# Loop_Mux_V2.net
KiCad netlist of a schematic drawn in EAGLE
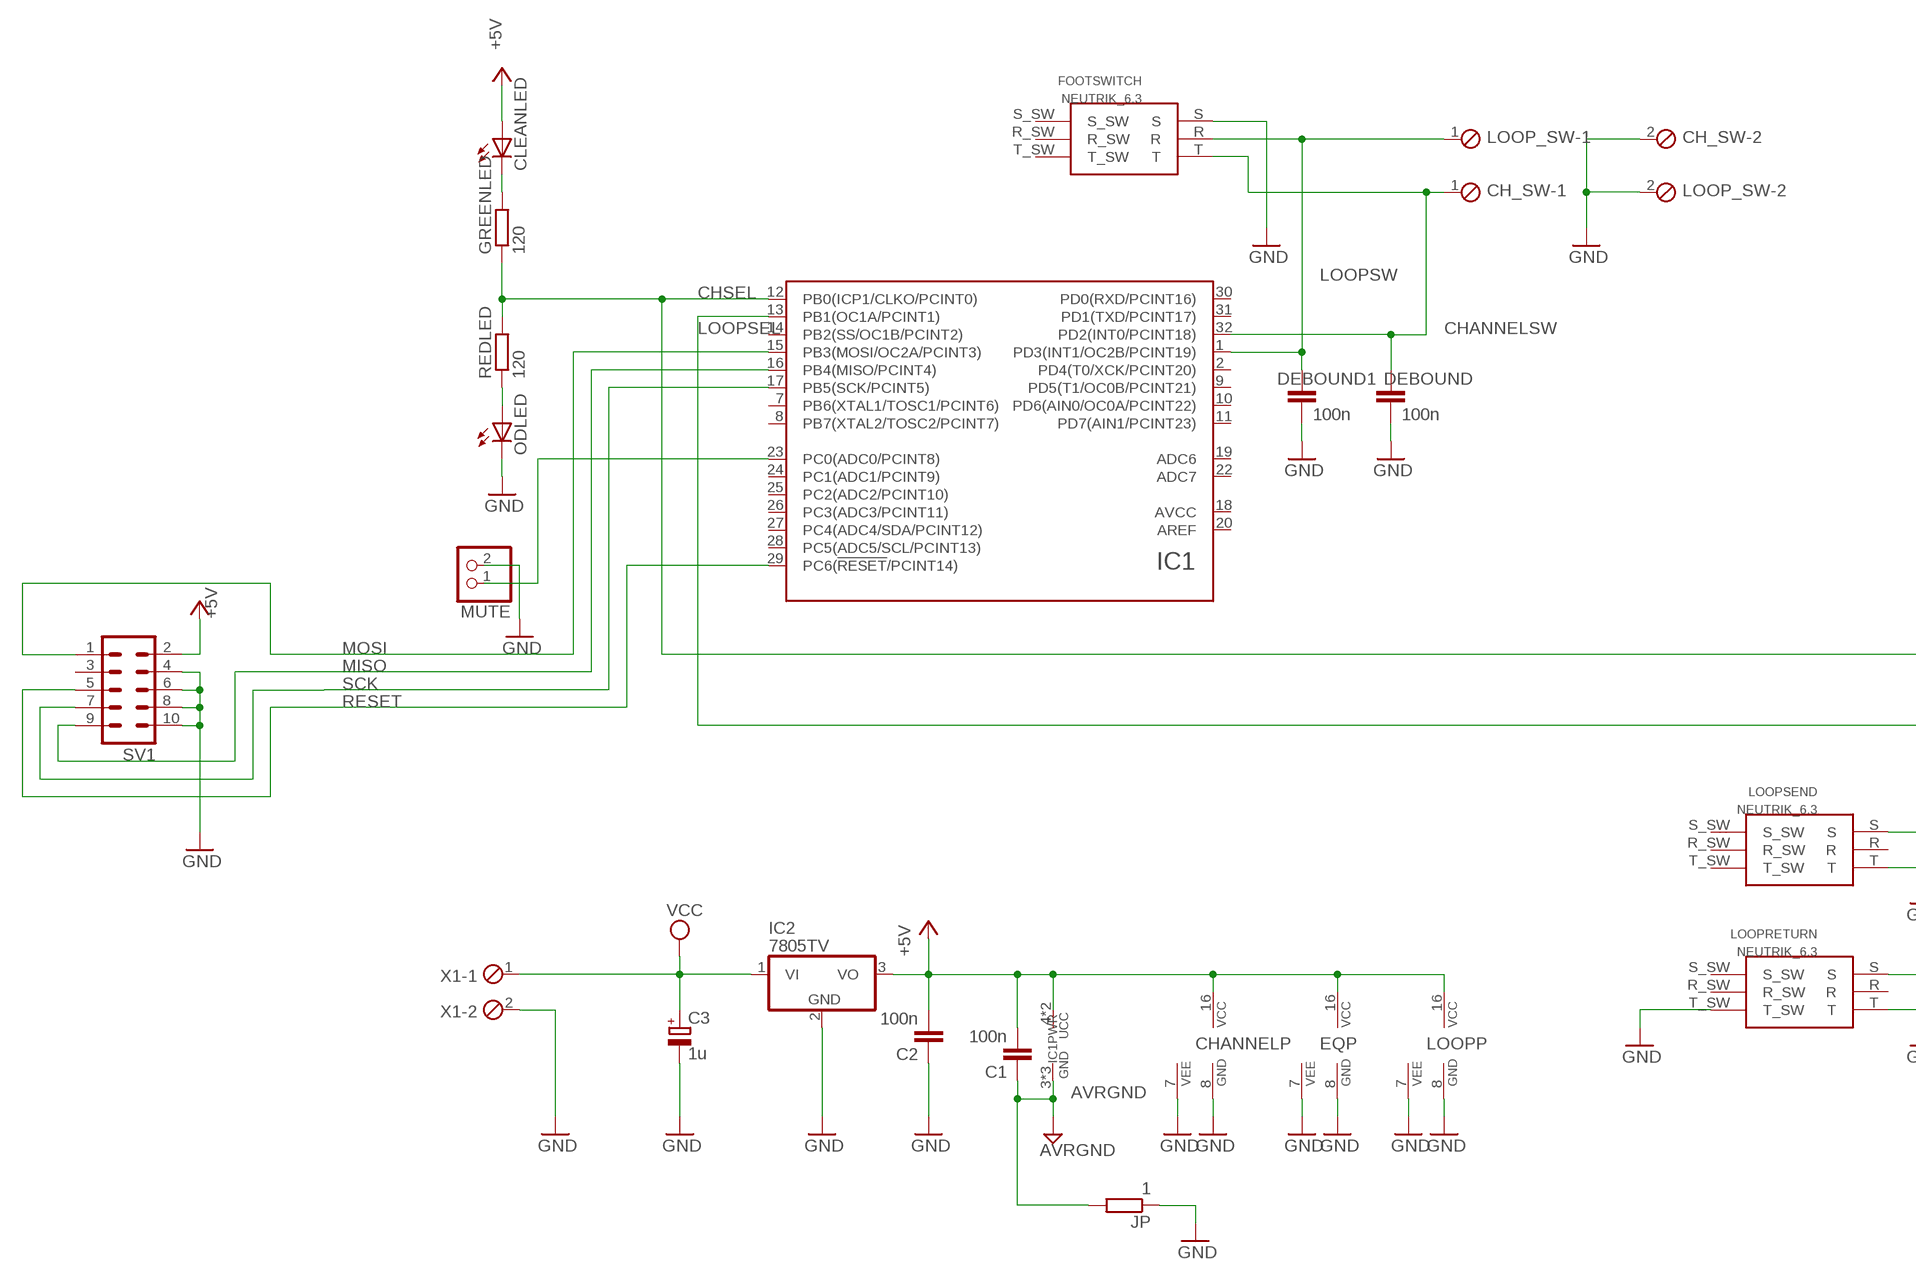
[diagram p0: schematic, sheet 1, part 1 of 2]
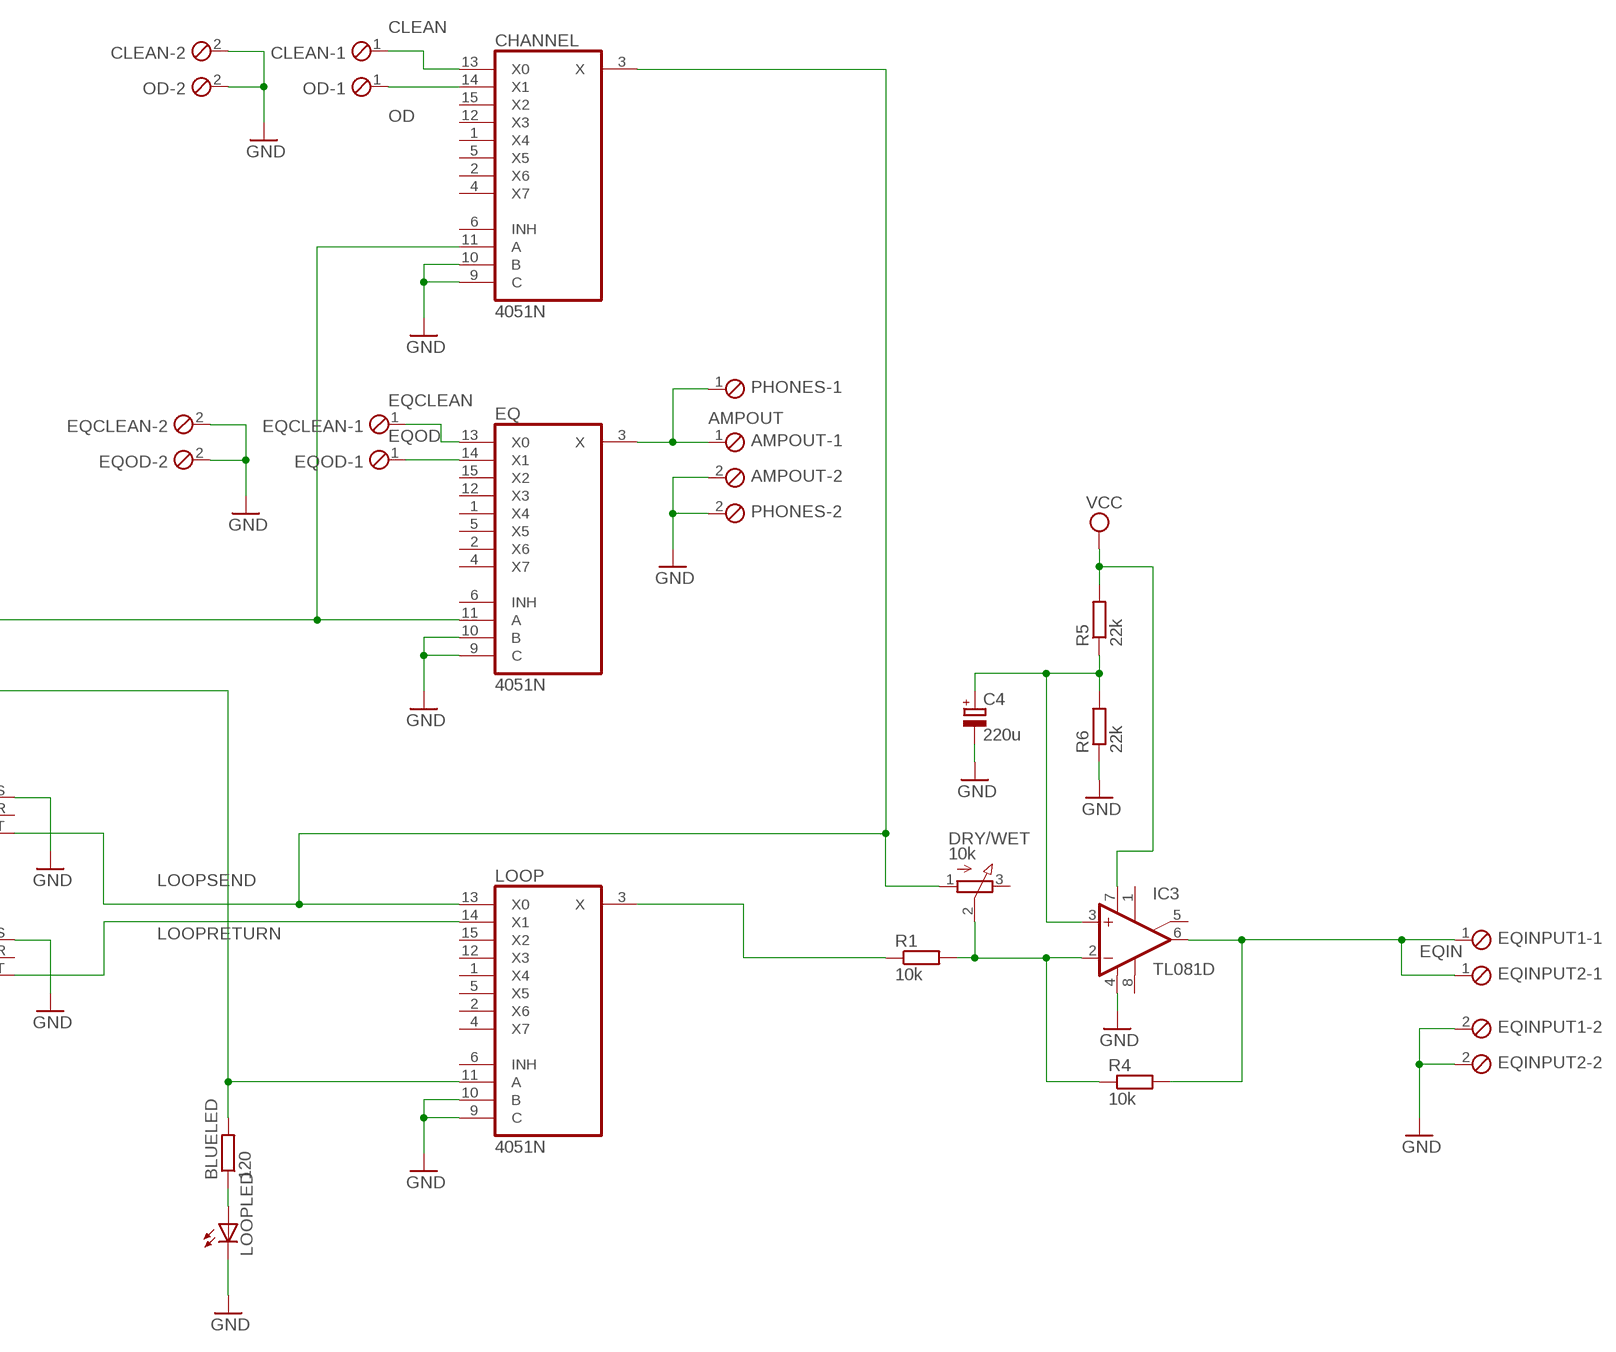
[diagram p1: schematic, sheet 1, part 2 of 2]

(export (version "E")
  (design (tool "Eeschema 10.0.6"))
  (components
    (comp (ref "AMPOUT")
      (value "MPT2")
      (footprint "eagle-import:2POL254")
      (libsource (lib "eagle-import") (part "MPT2"))
    )
    (comp (ref "BLUELED")
      (value "120")
      (footprint "eagle-import:R0805")
      (libsource (lib "eagle-import") (part "R-EU_R0805"))
    )
    (comp (ref "C1")
      (value "100n")
      (footprint "eagle-import:C1206")
      (libsource (lib "eagle-import") (part "C-EUC1206"))
    )
    (comp (ref "C2")
      (value "100n")
      (footprint "eagle-import:C1206")
      (libsource (lib "eagle-import") (part "C-EUC1206"))
    )
    (comp (ref "C3")
      (value "1u")
      (footprint "eagle-import:E2-5")
      (libsource (lib "eagle-import") (part "CPOL-EUE2-5"))
    )
    (comp (ref "C4")
      (value "220u")
      (footprint "eagle-import:E2,5-5")
      (libsource (lib "eagle-import") (part "CPOL-EUE2.5-5"))
    )
    (comp (ref "CHANNEL")
      (value "4051N")
      (footprint "eagle-import:DIL16")
      (libsource (lib "eagle-import") (part "4051N"))
    )
    (comp (ref "CH_SW")
      (value "MPT2")
      (footprint "eagle-import:2POL254")
      (libsource (lib "eagle-import") (part "MPT2"))
    )
    (comp (ref "CLEAN")
      (value "MPT2")
      (footprint "eagle-import:2POL254")
      (libsource (lib "eagle-import") (part "MPT2"))
    )
    (comp (ref "CLEANLED")
      (value "LED5MM")
      (footprint "eagle-import:LED5MM")
      (libsource (lib "eagle-import") (part "LED5MM"))
    )
    (comp (ref "DEBOUND")
      (value "100n")
      (footprint "eagle-import:C1206")
      (libsource (lib "eagle-import") (part "C-EUC1206"))
    )
    (comp (ref "DEBOUND1")
      (value "100n")
      (footprint "eagle-import:C1206")
      (libsource (lib "eagle-import") (part "C-EUC1206"))
    )
    (comp (ref "DRY/WET")
      (value "10k")
      (footprint "eagle-import:3RP_1610N")
      (libsource (lib "eagle-import") (part "3RP/1610N"))
    )
    (comp (ref "EQ")
      (value "4051N")
      (footprint "eagle-import:DIL16")
      (libsource (lib "eagle-import") (part "4051N"))
    )
    (comp (ref "EQCLEAN")
      (value "MPT2")
      (footprint "eagle-import:2POL254")
      (libsource (lib "eagle-import") (part "MPT2"))
    )
    (comp (ref "EQINPUT1")
      (value "MPT2")
      (footprint "eagle-import:2POL254")
      (libsource (lib "eagle-import") (part "MPT2"))
    )
    (comp (ref "EQINPUT2")
      (value "MPT2")
      (footprint "eagle-import:2POL254")
      (libsource (lib "eagle-import") (part "MPT2"))
    )
    (comp (ref "EQOD")
      (value "MPT2")
      (footprint "eagle-import:2POL254")
      (libsource (lib "eagle-import") (part "MPT2"))
    )
    (comp (ref "FOOTSWITCH")
      (value "NEUTRIK_6.3")
      (footprint "eagle-import:NEUTRIK_6.3")
      (libsource (lib "eagle-import") (part "NEUTRIK_6.3"))
    )
    (comp (ref "GREENLED")
      (value "120")
      (footprint "eagle-import:R0805")
      (libsource (lib "eagle-import") (part "R-EU_R0805"))
    )
    (comp (ref "IC1")
      (value "ATMEGA48/88/168/328-AU")
      (footprint "eagle-import:TQFP32-08")
      (libsource (lib "eagle-import") (part "ATMEGA48/88/168/328-AU"))
    )
    (comp (ref "IC2")
      (value "7805TV")
      (footprint "eagle-import:TO220V")
      (libsource (lib "eagle-import") (part "78TV05"))
    )
    (comp (ref "IC3")
      (value "TL081D")
      (footprint "eagle-import:SO08")
      (libsource (lib "eagle-import") (part "TL081D"))
    )
    (comp (ref "JP")
      (value "1")
      (footprint "eagle-import:R0805")
      (libsource (lib "eagle-import") (part "R-EU_R0805"))
    )
    (comp (ref "LOOP")
      (value "4051N")
      (footprint "eagle-import:DIL16")
      (libsource (lib "eagle-import") (part "4051N"))
    )
    (comp (ref "LOOPLED")
      (value "LED5MM")
      (footprint "eagle-import:LED5MM")
      (libsource (lib "eagle-import") (part "LED5MM"))
    )
    (comp (ref "LOOPRETURN")
      (value "NEUTRIK_6.3")
      (footprint "eagle-import:NEUTRIK_6.3")
      (libsource (lib "eagle-import") (part "NEUTRIK_6.3"))
    )
    (comp (ref "LOOPSEND")
      (value "NEUTRIK_6.3")
      (footprint "eagle-import:NEUTRIK_6.3")
      (libsource (lib "eagle-import") (part "NEUTRIK_6.3"))
    )
    (comp (ref "LOOP_SW")
      (value "MPT2")
      (footprint "eagle-import:2POL254")
      (libsource (lib "eagle-import") (part "MPT2"))
    )
    (comp (ref "MUTE")
      (value "PINHD-1X2")
      (footprint "eagle-import:1X02")
      (libsource (lib "eagle-import") (part "PINHD-1X2"))
    )
    (comp (ref "OD")
      (value "MPT2")
      (footprint "eagle-import:2POL254")
      (libsource (lib "eagle-import") (part "MPT2"))
    )
    (comp (ref "ODLED")
      (value "LED5MM")
      (footprint "eagle-import:LED5MM")
      (libsource (lib "eagle-import") (part "LED5MM"))
    )
    (comp (ref "PHONES")
      (value "MPT2")
      (footprint "eagle-import:2POL254")
      (libsource (lib "eagle-import") (part "MPT2"))
    )
    (comp (ref "R1")
      (value "10k")
      (footprint "eagle-import:R0805")
      (libsource (lib "eagle-import") (part "R-EU_R0805"))
    )
    (comp (ref "R4")
      (value "10k")
      (footprint "eagle-import:R0805")
      (libsource (lib "eagle-import") (part "R-EU_R0805"))
    )
    (comp (ref "R5")
      (value "22k")
      (footprint "eagle-import:R0805")
      (libsource (lib "eagle-import") (part "R-EU_R0805"))
    )
    (comp (ref "R6")
      (value "22k")
      (footprint "eagle-import:R0805")
      (libsource (lib "eagle-import") (part "R-EU_R0805"))
    )
    (comp (ref "REDLED")
      (value "120")
      (footprint "eagle-import:R0805")
      (libsource (lib "eagle-import") (part "R-EU_R0805"))
    )
    (comp (ref "SV1")
      (value "MA05-2")
      (footprint "eagle-import:MA05-2")
      (libsource (lib "eagle-import") (part "MA05-2"))
    )
    (comp (ref "X1")
      (value "MPT2")
      (footprint "eagle-import:2POL254")
      (libsource (lib "eagle-import") (part "MPT2"))
    )
  )
  (nets
    (net (code "1") (name "+5V") (class "Default")
      (node (ref "C1") (pin "2") (pinfunction "2_2") (pintype "passive"))
      (node (ref "C2") (pin "2") (pinfunction "2_2") (pintype "passive"))
      (node (ref "CHANNEL") (pin "16") (pinfunction "VCC_16") (pintype "power_in"))
      (node (ref "CLEANLED") (pin "A") (pinfunction "A_A") (pintype "passive"))
      (node (ref "EQ") (pin "16") (pinfunction "VCC_16") (pintype "power_in"))
      (node (ref "IC1") (pin "4") (pinfunction "UCC_4") (pintype "power_in"))
      (node (ref "IC1") (pin "6") (pinfunction "UCC_6") (pintype "power_in"))
      (node (ref "IC2") (pin "3") (pinfunction "VO_3") (pintype "passive"))
      (node (ref "LOOP") (pin "16") (pinfunction "VCC_16") (pintype "power_in"))
      (node (ref "SV1") (pin "2") (pinfunction "2_2") (pintype "passive"))
    )
    (net (code "2") (name "/AMPOUT") (class "Default")
      (node (ref "AMPOUT") (pin "1") (pinfunction "1_1") (pintype "passive"))
      (node (ref "EQ") (pin "3") (pinfunction "X_3") (pintype "bidirectional"))
      (node (ref "PHONES") (pin "1") (pinfunction "1_1") (pintype "passive"))
    )
    (net (code "3") (name "/AVCC") (class "Default")
      (node (ref "IC1") (pin "18") (pinfunction "AVCC_18") (pintype "power_in"))
    )
    (net (code "4") (name "/CHANNELSW") (class "Default")
      (node (ref "CH_SW") (pin "1") (pinfunction "1_1") (pintype "passive"))
      (node (ref "DEBOUND") (pin "1") (pinfunction "1_1") (pintype "passive"))
      (node (ref "FOOTSWITCH") (pin "T") (pinfunction "T_T") (pintype "bidirectional"))
      (node (ref "IC1") (pin "32") (pinfunction "PD2(INT0/PCINT18)_32") (pintype "bidirectional"))
    )
    (net (code "5") (name "/CHSEL") (class "Default")
      (node (ref "CHANNEL") (pin "11") (pinfunction "A_11") (pintype "input"))
      (node (ref "EQ") (pin "11") (pinfunction "A_11") (pintype "input"))
      (node (ref "GREENLED") (pin "1") (pinfunction "1_1") (pintype "passive"))
      (node (ref "IC1") (pin "12") (pinfunction "PB0(ICP1/CLKO/PCINT0)_12") (pintype "bidirectional"))
      (node (ref "REDLED") (pin "2") (pinfunction "2_2") (pintype "passive"))
    )
    (net (code "6") (name "/CLEAN") (class "Default")
      (node (ref "CHANNEL") (pin "13") (pinfunction "X0_13") (pintype "bidirectional"))
      (node (ref "CLEAN") (pin "1") (pinfunction "1_1") (pintype "passive"))
    )
    (net (code "7") (name "/EQCLEAN") (class "Default")
      (node (ref "EQ") (pin "13") (pinfunction "X0_13") (pintype "bidirectional"))
      (node (ref "EQCLEAN") (pin "1") (pinfunction "1_1") (pintype "passive"))
    )
    (net (code "8") (name "/EQIN") (class "Default")
      (node (ref "EQINPUT1") (pin "1") (pinfunction "1_1") (pintype "passive"))
      (node (ref "EQINPUT2") (pin "1") (pinfunction "1_1") (pintype "passive"))
      (node (ref "IC3") (pin "6") (pinfunction "OUT_6") (pintype "output"))
      (node (ref "R4") (pin "2") (pinfunction "2_2") (pintype "passive"))
    )
    (net (code "9") (name "/EQOD") (class "Default")
      (node (ref "EQ") (pin "14") (pinfunction "X1_14") (pintype "bidirectional"))
      (node (ref "EQOD") (pin "1") (pinfunction "1_1") (pintype "passive"))
    )
    (net (code "10") (name "/LOOPRETURN") (class "Default")
      (node (ref "LOOP") (pin "14") (pinfunction "X1_14") (pintype "bidirectional"))
      (node (ref "LOOPRETURN") (pin "T") (pinfunction "T_T") (pintype "bidirectional"))
    )
    (net (code "11") (name "/LOOPSEL") (class "Default")
      (node (ref "BLUELED") (pin "2") (pinfunction "2_2") (pintype "passive"))
      (node (ref "IC1") (pin "13") (pinfunction "PB1(OC1A/PCINT1)_13") (pintype "bidirectional"))
      (node (ref "LOOP") (pin "11") (pinfunction "A_11") (pintype "input"))
    )
    (net (code "12") (name "/LOOPSEND") (class "Default")
      (node (ref "CHANNEL") (pin "3") (pinfunction "X_3") (pintype "bidirectional"))
      (node (ref "DRY/WET") (pin "1") (pinfunction "A_1") (pintype "passive"))
      (node (ref "LOOP") (pin "13") (pinfunction "X0_13") (pintype "bidirectional"))
      (node (ref "LOOPSEND") (pin "T") (pinfunction "T_T") (pintype "bidirectional"))
    )
    (net (code "13") (name "/LOOPSW") (class "Default")
      (node (ref "DEBOUND1") (pin "1") (pinfunction "1_1") (pintype "passive"))
      (node (ref "FOOTSWITCH") (pin "R") (pinfunction "R_R") (pintype "bidirectional"))
      (node (ref "IC1") (pin "1") (pinfunction "PD3(INT1/OC2B/PCINT19)_1") (pintype "bidirectional"))
      (node (ref "LOOP_SW") (pin "1") (pinfunction "1_1") (pintype "passive"))
    )
    (net (code "14") (name "/MISO") (class "Default")
      (node (ref "IC1") (pin "16") (pinfunction "PB4(MISO/PCINT4)_16") (pintype "bidirectional"))
      (node (ref "SV1") (pin "9") (pinfunction "9_9") (pintype "passive"))
    )
    (net (code "15") (name "/MOSI") (class "Default")
      (node (ref "IC1") (pin "15") (pinfunction "PB3(MOSI/OC2A/PCINT3)_15") (pintype "bidirectional"))
      (node (ref "SV1") (pin "1") (pinfunction "1_1") (pintype "passive"))
    )
    (net (code "16") (name "/OD") (class "Default")
      (node (ref "CHANNEL") (pin "14") (pinfunction "X1_14") (pintype "bidirectional"))
      (node (ref "OD") (pin "1") (pinfunction "1_1") (pintype "passive"))
    )
    (net (code "17") (name "/RESET") (class "Default")
      (node (ref "IC1") (pin "29") (pinfunction "PC6(~{RESET}/PCINT14)_29") (pintype "bidirectional"))
      (node (ref "SV1") (pin "5") (pinfunction "5_5") (pintype "passive"))
    )
    (net (code "18") (name "/SCK") (class "Default")
      (node (ref "IC1") (pin "17") (pinfunction "PB5(SCK/PCINT5)_17") (pintype "bidirectional"))
      (node (ref "SV1") (pin "7") (pinfunction "7_7") (pintype "passive"))
    )
    (net (code "19") (name "AVRGND") (class "Default")
      (node (ref "C1") (pin "1") (pinfunction "1_1") (pintype "passive"))
      (node (ref "IC1") (pin "21") (pinfunction "GND_21") (pintype "power_in"))
      (node (ref "IC1") (pin "3") (pinfunction "GND_3") (pintype "power_in"))
      (node (ref "IC1") (pin "5") (pinfunction "GND_5") (pintype "power_in"))
      (node (ref "JP") (pin "2") (pinfunction "2_2") (pintype "passive"))
    )
    (net (code "20") (name "GND") (class "Default")
      (node (ref "AMPOUT") (pin "2") (pinfunction "1_2") (pintype "passive"))
      (node (ref "C2") (pin "1") (pinfunction "1_1") (pintype "passive"))
      (node (ref "C3") (pin "-") (pinfunction "-_-") (pintype "passive"))
      (node (ref "C4") (pin "-") (pinfunction "-_-") (pintype "passive"))
      (node (ref "CHANNEL") (pin "10") (pinfunction "B_10") (pintype "input"))
      (node (ref "CHANNEL") (pin "7") (pinfunction "VEE_7") (pintype "power_in"))
      (node (ref "CHANNEL") (pin "8") (pinfunction "GND_8") (pintype "power_in"))
      (node (ref "CHANNEL") (pin "9") (pinfunction "C_9") (pintype "input"))
      (node (ref "CH_SW") (pin "2") (pinfunction "1_2") (pintype "passive"))
      (node (ref "CLEAN") (pin "2") (pinfunction "1_2") (pintype "passive"))
      (node (ref "DEBOUND") (pin "2") (pinfunction "2_2") (pintype "passive"))
      (node (ref "DEBOUND1") (pin "2") (pinfunction "2_2") (pintype "passive"))
      (node (ref "EQ") (pin "10") (pinfunction "B_10") (pintype "input"))
      (node (ref "EQ") (pin "7") (pinfunction "VEE_7") (pintype "power_in"))
      (node (ref "EQ") (pin "8") (pinfunction "GND_8") (pintype "power_in"))
      (node (ref "EQ") (pin "9") (pinfunction "C_9") (pintype "input"))
      (node (ref "EQCLEAN") (pin "2") (pinfunction "1_2") (pintype "passive"))
      (node (ref "EQINPUT1") (pin "2") (pinfunction "1_2") (pintype "passive"))
      (node (ref "EQINPUT2") (pin "2") (pinfunction "1_2") (pintype "passive"))
      (node (ref "EQOD") (pin "2") (pinfunction "1_2") (pintype "passive"))
      (node (ref "FOOTSWITCH") (pin "S") (pinfunction "S_S") (pintype "bidirectional"))
      (node (ref "IC2") (pin "2") (pinfunction "GND_2") (pintype "passive"))
      (node (ref "IC3") (pin "4") (pinfunction "V-_4") (pintype "power_in"))
      (node (ref "JP") (pin "1") (pinfunction "1_1") (pintype "passive"))
      (node (ref "LOOP") (pin "10") (pinfunction "B_10") (pintype "input"))
      (node (ref "LOOP") (pin "7") (pinfunction "VEE_7") (pintype "power_in"))
      (node (ref "LOOP") (pin "8") (pinfunction "GND_8") (pintype "power_in"))
      (node (ref "LOOP") (pin "9") (pinfunction "C_9") (pintype "input"))
      (node (ref "LOOPLED") (pin "K") (pinfunction "C_K") (pintype "passive"))
      (node (ref "LOOPRETURN") (pin "S") (pinfunction "S_S") (pintype "bidirectional"))
      (node (ref "LOOPRETURN") (pin "T_SW") (pinfunction "T_SW_T_SW") (pintype "bidirectional"))
      (node (ref "LOOPSEND") (pin "S") (pinfunction "S_S") (pintype "bidirectional"))
      (node (ref "LOOP_SW") (pin "2") (pinfunction "1_2") (pintype "passive"))
      (node (ref "MUTE") (pin "2") (pinfunction "2_2") (pintype "passive"))
      (node (ref "OD") (pin "2") (pinfunction "1_2") (pintype "passive"))
      (node (ref "ODLED") (pin "K") (pinfunction "C_K") (pintype "passive"))
      (node (ref "PHONES") (pin "2") (pinfunction "1_2") (pintype "passive"))
      (node (ref "R6") (pin "1") (pinfunction "1_1") (pintype "passive"))
      (node (ref "SV1") (pin "10") (pinfunction "10_10") (pintype "passive"))
      (node (ref "SV1") (pin "4") (pinfunction "4_4") (pintype "passive"))
      (node (ref "SV1") (pin "6") (pinfunction "6_6") (pintype "passive"))
      (node (ref "SV1") (pin "8") (pinfunction "8_8") (pintype "passive"))
      (node (ref "X1") (pin "2") (pinfunction "1_2") (pintype "passive"))
    )
    (net (code "21") (name "Net-(BLUELED-Pad1)") (class "Default")
      (node (ref "BLUELED") (pin "1") (pinfunction "1_1") (pintype "passive"))
      (node (ref "LOOPLED") (pin "A") (pinfunction "A_A") (pintype "passive"))
    )
    (net (code "22") (name "Net-(CLEANLED-C)") (class "Default")
      (node (ref "CLEANLED") (pin "K") (pinfunction "C_K") (pintype "passive"))
      (node (ref "GREENLED") (pin "2") (pinfunction "2_2") (pintype "passive"))
    )
    (net (code "23") (name "Net-(DRY/WET-S)") (class "Default")
      (node (ref "DRY/WET") (pin "2") (pinfunction "S_2") (pintype "passive"))
      (node (ref "IC3") (pin "2") (pinfunction "-IN_2") (pintype "input"))
      (node (ref "R1") (pin "2") (pinfunction "2_2") (pintype "passive"))
      (node (ref "R4") (pin "1") (pinfunction "1_1") (pintype "passive"))
    )
    (net (code "24") (name "Net-(IC1A-PC0(ADC0{slash}PCINT8))") (class "Default")
      (node (ref "IC1") (pin "23") (pinfunction "PC0(ADC0/PCINT8)_23") (pintype "bidirectional"))
      (node (ref "MUTE") (pin "1") (pinfunction "1_1") (pintype "passive"))
    )
    (net (code "25") (name "Net-(IC3-+IN)") (class "Default")
      (node (ref "C4") (pin "+") (pinfunction "+_+") (pintype "passive"))
      (node (ref "IC3") (pin "3") (pinfunction "+IN_3") (pintype "input"))
      (node (ref "R5") (pin "1") (pinfunction "1_1") (pintype "passive"))
      (node (ref "R6") (pin "2") (pinfunction "2_2") (pintype "passive"))
    )
    (net (code "26") (name "Net-(LOOPA-X)") (class "Default")
      (node (ref "LOOP") (pin "3") (pinfunction "X_3") (pintype "bidirectional"))
      (node (ref "R1") (pin "1") (pinfunction "1_1") (pintype "passive"))
    )
    (net (code "27") (name "Net-(ODLED-PadA)") (class "Default")
      (node (ref "ODLED") (pin "A") (pinfunction "A_A") (pintype "passive"))
      (node (ref "REDLED") (pin "1") (pinfunction "1_1") (pintype "passive"))
    )
    (net (code "28") (name "VCC") (class "Default")
      (node (ref "C3") (pin "+") (pinfunction "+_+") (pintype "passive"))
      (node (ref "IC2") (pin "1") (pinfunction "VI_1") (pintype "input"))
      (node (ref "IC3") (pin "7") (pinfunction "V+_7") (pintype "power_in"))
      (node (ref "R5") (pin "2") (pinfunction "2_2") (pintype "passive"))
      (node (ref "X1") (pin "1") (pinfunction "1_1") (pintype "passive"))
    )
    (net (code "29") (name "unconnected-(CHANNELA-INH-Pad6)") (class "Default")
      (node (ref "CHANNEL") (pin "6") (pinfunction "INH_6") (pintype "input"))
    )
    (net (code "30") (name "unconnected-(CHANNELA-X2-Pad15)") (class "Default")
      (node (ref "CHANNEL") (pin "15") (pinfunction "X2_15") (pintype "bidirectional"))
    )
    (net (code "31") (name "unconnected-(CHANNELA-X3-Pad12)") (class "Default")
      (node (ref "CHANNEL") (pin "12") (pinfunction "X3_12") (pintype "bidirectional"))
    )
    (net (code "32") (name "unconnected-(CHANNELA-X4-Pad1)") (class "Default")
      (node (ref "CHANNEL") (pin "1") (pinfunction "X4_1") (pintype "bidirectional"))
    )
    (net (code "33") (name "unconnected-(CHANNELA-X5-Pad5)") (class "Default")
      (node (ref "CHANNEL") (pin "5") (pinfunction "X5_5") (pintype "bidirectional"))
    )
    (net (code "34") (name "unconnected-(CHANNELA-X6-Pad2)") (class "Default")
      (node (ref "CHANNEL") (pin "2") (pinfunction "X6_2") (pintype "bidirectional"))
    )
    (net (code "35") (name "unconnected-(CHANNELA-X7-Pad4)") (class "Default")
      (node (ref "CHANNEL") (pin "4") (pinfunction "X7_4") (pintype "bidirectional"))
    )
    (net (code "36") (name "unconnected-(DRY/WET-E-Pad3)") (class "Default")
      (node (ref "DRY/WET") (pin "3") (pinfunction "E_3") (pintype "passive"))
    )
    (net (code "37") (name "unconnected-(EQA-INH-Pad6)") (class "Default")
      (node (ref "EQ") (pin "6") (pinfunction "INH_6") (pintype "input"))
    )
    (net (code "38") (name "unconnected-(EQA-X2-Pad15)") (class "Default")
      (node (ref "EQ") (pin "15") (pinfunction "X2_15") (pintype "bidirectional"))
    )
    (net (code "39") (name "unconnected-(EQA-X3-Pad12)") (class "Default")
      (node (ref "EQ") (pin "12") (pinfunction "X3_12") (pintype "bidirectional"))
    )
    (net (code "40") (name "unconnected-(EQA-X4-Pad1)") (class "Default")
      (node (ref "EQ") (pin "1") (pinfunction "X4_1") (pintype "bidirectional"))
    )
    (net (code "41") (name "unconnected-(EQA-X5-Pad5)") (class "Default")
      (node (ref "EQ") (pin "5") (pinfunction "X5_5") (pintype "bidirectional"))
    )
    (net (code "42") (name "unconnected-(EQA-X6-Pad2)") (class "Default")
      (node (ref "EQ") (pin "2") (pinfunction "X6_2") (pintype "bidirectional"))
    )
    (net (code "43") (name "unconnected-(EQA-X7-Pad4)") (class "Default")
      (node (ref "EQ") (pin "4") (pinfunction "X7_4") (pintype "bidirectional"))
    )
    (net (code "44") (name "unconnected-(FOOTSWITCH-PadR_SW)") (class "Default")
      (node (ref "FOOTSWITCH") (pin "R_SW") (pinfunction "R_SW_R_SW") (pintype "bidirectional"))
    )
    (net (code "45") (name "unconnected-(FOOTSWITCH-PadS_SW)") (class "Default")
      (node (ref "FOOTSWITCH") (pin "S_SW") (pinfunction "S_SW_S_SW") (pintype "bidirectional"))
    )
    (net (code "46") (name "unconnected-(FOOTSWITCH-PadT_SW)") (class "Default")
      (node (ref "FOOTSWITCH") (pin "T_SW") (pinfunction "T_SW_T_SW") (pintype "bidirectional"))
    )
    (net (code "47") (name "unconnected-(IC1A-ADC6-Pad19)") (class "Default")
      (node (ref "IC1") (pin "19") (pinfunction "ADC6_19") (pintype "passive"))
    )
    (net (code "48") (name "unconnected-(IC1A-ADC7-Pad22)") (class "Default")
      (node (ref "IC1") (pin "22") (pinfunction "ADC7_22") (pintype "passive"))
    )
    (net (code "49") (name "unconnected-(IC1A-AREF-Pad20)") (class "Default")
      (node (ref "IC1") (pin "20") (pinfunction "AREF_20") (pintype "passive"))
    )
    (net (code "50") (name "unconnected-(IC1A-PB2(SS{slash}OC1B{slash}PCINT2)-Pad14)") (class "Default")
      (node (ref "IC1") (pin "14") (pinfunction "PB2(SS/OC1B/PCINT2)_14") (pintype "bidirectional"))
    )
    (net (code "51") (name "unconnected-(IC1A-PB6(XTAL1{slash}TOSC1{slash}PCINT6)-Pad7)") (class "Default")
      (node (ref "IC1") (pin "7") (pinfunction "PB6(XTAL1/TOSC1/PCINT6)_7") (pintype "bidirectional"))
    )
    (net (code "52") (name "unconnected-(IC1A-PB7(XTAL2{slash}TOSC2{slash}PCINT7)-Pad8)") (class "Default")
      (node (ref "IC1") (pin "8") (pinfunction "PB7(XTAL2/TOSC2/PCINT7)_8") (pintype "bidirectional"))
    )
    (net (code "53") (name "unconnected-(IC1A-PC1(ADC1{slash}PCINT9)-Pad24)") (class "Default")
      (node (ref "IC1") (pin "24") (pinfunction "PC1(ADC1/PCINT9)_24") (pintype "bidirectional"))
    )
    (net (code "54") (name "unconnected-(IC1A-PC2(ADC2{slash}PCINT10)-Pad25)") (class "Default")
      (node (ref "IC1") (pin "25") (pinfunction "PC2(ADC2/PCINT10)_25") (pintype "bidirectional"))
    )
    (net (code "55") (name "unconnected-(IC1A-PC3(ADC3{slash}PCINT11)-Pad26)") (class "Default")
      (node (ref "IC1") (pin "26") (pinfunction "PC3(ADC3/PCINT11)_26") (pintype "bidirectional"))
    )
    (net (code "56") (name "unconnected-(IC1A-PC4(ADC4{slash}SDA{slash}PCINT12)-Pad27)") (class "Default")
      (node (ref "IC1") (pin "27") (pinfunction "PC4(ADC4/SDA/PCINT12)_27") (pintype "bidirectional"))
    )
    (net (code "57") (name "unconnected-(IC1A-PC5(ADC5{slash}SCL{slash}PCINT13)-Pad28)") (class "Default")
      (node (ref "IC1") (pin "28") (pinfunction "PC5(ADC5/SCL/PCINT13)_28") (pintype "bidirectional"))
    )
    (net (code "58") (name "unconnected-(IC1A-PD0(RXD{slash}PCINT16)-Pad30)") (class "Default")
      (node (ref "IC1") (pin "30") (pinfunction "PD0(RXD/PCINT16)_30") (pintype "bidirectional"))
    )
    (net (code "59") (name "unconnected-(IC1A-PD1(TXD{slash}PCINT17)-Pad31)") (class "Default")
      (node (ref "IC1") (pin "31") (pinfunction "PD1(TXD/PCINT17)_31") (pintype "bidirectional"))
    )
    (net (code "60") (name "unconnected-(IC1A-PD4(T0{slash}XCK{slash}PCINT20)-Pad2)") (class "Default")
      (node (ref "IC1") (pin "2") (pinfunction "PD4(T0/XCK/PCINT20)_2") (pintype "bidirectional"))
    )
    (net (code "61") (name "unconnected-(IC1A-PD5(T1{slash}OC0B{slash}PCINT21)-Pad9)") (class "Default")
      (node (ref "IC1") (pin "9") (pinfunction "PD5(T1/OC0B/PCINT21)_9") (pintype "bidirectional"))
    )
    (net (code "62") (name "unconnected-(IC1A-PD6(AIN0{slash}OC0A{slash}PCINT22)-Pad10)") (class "Default")
      (node (ref "IC1") (pin "10") (pinfunction "PD6(AIN0/OC0A/PCINT22)_10") (pintype "bidirectional"))
    )
    (net (code "63") (name "unconnected-(IC1A-PD7(AIN1{slash}PCINT23)-Pad11)") (class "Default")
      (node (ref "IC1") (pin "11") (pinfunction "PD7(AIN1/PCINT23)_11") (pintype "bidirectional"))
    )
    (net (code "64") (name "unconnected-(IC3-ON1-Pad1)") (class "Default")
      (node (ref "IC3") (pin "1") (pinfunction "ON1_1") (pintype "passive"))
    )
    (net (code "65") (name "unconnected-(IC3-ON2-Pad5)") (class "Default")
      (node (ref "IC3") (pin "5") (pinfunction "ON2_5") (pintype "passive"))
    )
    (net (code "66") (name "unconnected-(IC3-OPT-Pad8)") (class "Default")
      (node (ref "IC3") (pin "8") (pinfunction "OPT_8") (pintype "passive"))
    )
    (net (code "67") (name "unconnected-(LOOPA-INH-Pad6)") (class "Default")
      (node (ref "LOOP") (pin "6") (pinfunction "INH_6") (pintype "input"))
    )
    (net (code "68") (name "unconnected-(LOOPA-X2-Pad15)") (class "Default")
      (node (ref "LOOP") (pin "15") (pinfunction "X2_15") (pintype "bidirectional"))
    )
    (net (code "69") (name "unconnected-(LOOPA-X3-Pad12)") (class "Default")
      (node (ref "LOOP") (pin "12") (pinfunction "X3_12") (pintype "bidirectional"))
    )
    (net (code "70") (name "unconnected-(LOOPA-X4-Pad1)") (class "Default")
      (node (ref "LOOP") (pin "1") (pinfunction "X4_1") (pintype "bidirectional"))
    )
    (net (code "71") (name "unconnected-(LOOPA-X5-Pad5)") (class "Default")
      (node (ref "LOOP") (pin "5") (pinfunction "X5_5") (pintype "bidirectional"))
    )
    (net (code "72") (name "unconnected-(LOOPA-X6-Pad2)") (class "Default")
      (node (ref "LOOP") (pin "2") (pinfunction "X6_2") (pintype "bidirectional"))
    )
    (net (code "73") (name "unconnected-(LOOPA-X7-Pad4)") (class "Default")
      (node (ref "LOOP") (pin "4") (pinfunction "X7_4") (pintype "bidirectional"))
    )
    (net (code "74") (name "unconnected-(LOOPRETURN-PadR)") (class "Default")
      (node (ref "LOOPRETURN") (pin "R") (pinfunction "R_R") (pintype "bidirectional"))
    )
    (net (code "75") (name "unconnected-(LOOPRETURN-PadR_SW)") (class "Default")
      (node (ref "LOOPRETURN") (pin "R_SW") (pinfunction "R_SW_R_SW") (pintype "bidirectional"))
    )
    (net (code "76") (name "unconnected-(LOOPRETURN-PadS_SW)") (class "Default")
      (node (ref "LOOPRETURN") (pin "S_SW") (pinfunction "S_SW_S_SW") (pintype "bidirectional"))
    )
    (net (code "77") (name "unconnected-(LOOPSEND-PadR)") (class "Default")
      (node (ref "LOOPSEND") (pin "R") (pinfunction "R_R") (pintype "bidirectional"))
    )
    (net (code "78") (name "unconnected-(LOOPSEND-PadR_SW)") (class "Default")
      (node (ref "LOOPSEND") (pin "R_SW") (pinfunction "R_SW_R_SW") (pintype "bidirectional"))
    )
    (net (code "79") (name "unconnected-(LOOPSEND-PadS_SW)") (class "Default")
      (node (ref "LOOPSEND") (pin "S_SW") (pinfunction "S_SW_S_SW") (pintype "bidirectional"))
    )
    (net (code "80") (name "unconnected-(LOOPSEND-PadT_SW)") (class "Default")
      (node (ref "LOOPSEND") (pin "T_SW") (pinfunction "T_SW_T_SW") (pintype "bidirectional"))
    )
    (net (code "81") (name "unconnected-(SV1-Pad3)") (class "Default")
      (node (ref "SV1") (pin "3") (pinfunction "3_3") (pintype "passive"))
    )
  )
)
